# RR_MXR_v1.net
KiCad netlist of a schematic drawn in Altium Designer
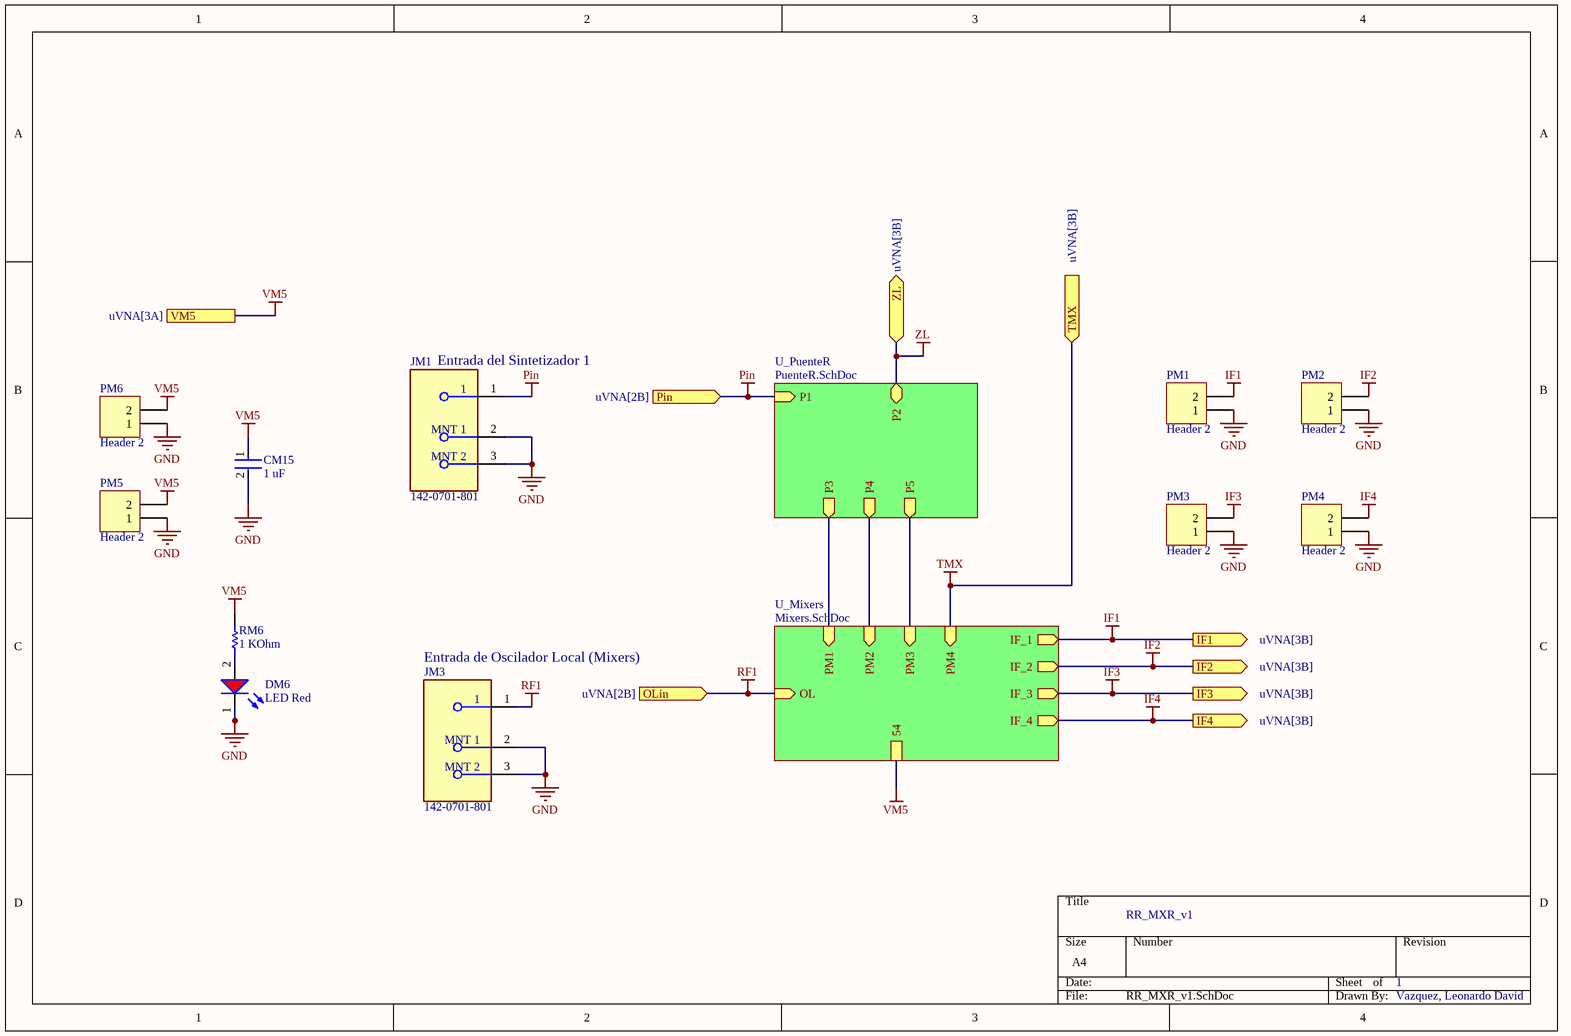
[diagram p0: RR_MXR_v1.SchDoc]

(export (version "E")
  (design (tool "Eeschema 10.0.6"))
  (components
    (comp (ref "CM15")
      (value "1 uF")
      (footprint "FP-CC0805-0_85-MFG")
      (description "CAP CER 0.1UF 50V X7R 0805")
      (fields (field (name "TOLERANCE") "0.1") (field (name "MANUFACTURER PART NUMBER") "CC0805KRX7R9BB104"))
      (libsource (lib "Altium Content Vault") (part "11868f565c42a9108669ba33697ecf6"))
    )
    (comp (ref "DM6")
      (value "LED Red")
      (footprint "WL-SMCW_0805_150080xx75000")
      (libsource (lib "Altium Content Vault") (part "LED_Red_2A-1K"))
    )
    (comp (ref "JM1")
      (value "142-0701-801")
      (footprint "FP-142-0701-801-MFG")
      (description "CONN SMA JACK STR 50OHM EDGE MNT")
      (libsource (lib "Altium Content Vault") (part "89929399afe843c8b6880c6cbd0f99a"))
    )
    (comp (ref "JM3")
      (value "142-0701-801")
      (footprint "FP-142-0701-801-MFG")
      (description "CONN SMA JACK STR 50OHM EDGE MNT")
      (libsource (lib "Altium Content Vault") (part "89929399afe843c8b6880c6cbd0f99a"))
    )
    (comp (ref "PM1")
      (value "Header 2")
      (footprint "HDR1X2")
      (description "Header, 2-Pin")
      (fields (field (name "PUBLISHER") "Altium Limited"))
      (libsource (lib "Miscellaneous Connectors") (part "Header 2"))
    )
    (comp (ref "PM2")
      (value "Header 2")
      (footprint "HDR1X2")
      (description "Header, 2-Pin")
      (fields (field (name "PUBLISHER") "Altium Limited"))
      (libsource (lib "Miscellaneous Connectors") (part "Header 2"))
    )
    (comp (ref "PM3")
      (value "Header 2")
      (footprint "HDR1X2")
      (description "Header, 2-Pin")
      (fields (field (name "PUBLISHER") "Altium Limited"))
      (libsource (lib "Miscellaneous Connectors") (part "Header 2"))
    )
    (comp (ref "PM4")
      (value "Header 2")
      (footprint "HDR1X2")
      (description "Header, 2-Pin")
      (fields (field (name "PUBLISHER") "Altium Limited"))
      (libsource (lib "Miscellaneous Connectors") (part "Header 2"))
    )
    (comp (ref "PM5")
      (value "Header 2")
      (footprint "HDR1X2")
      (description "Header, 2-Pin")
      (fields (field (name "PUBLISHER") "Altium Limited"))
      (libsource (lib "Miscellaneous Connectors") (part "Header 2"))
    )
    (comp (ref "PM6")
      (value "Header 2")
      (footprint "HDR1X2")
      (description "Header, 2-Pin")
      (fields (field (name "PUBLISHER") "Altium Limited"))
      (libsource (lib "Miscellaneous Connectors") (part "Header 2"))
    )
    (comp (ref "RM6")
      (value "1 KOhm")
      (footprint "RESC2013X60X40ML20T25")
      (fields (field (name "MANUFACTURER") "Panasonic") (field (name "PART NUMBER") "ERA6AEB101V"))
      (libsource (lib "Altium Content Vault") (part "RES"))
    )
  )
  (nets
    (net (code "4") (name "GND") (class "Default")
      (node (ref "CM15") (pin "2") (pinfunction "2_2") (pintype "passive"))
      (node (ref "DM6") (pin "1") (pinfunction "K_1") (pintype "passive"))
      (node (ref "JM1") (pin "2") (pinfunction "MNT_1_2") (pintype "passive"))
      (node (ref "JM1") (pin "3") (pinfunction "MNT_2_3") (pintype "passive"))
      (node (ref "JM3") (pin "2") (pinfunction "MNT_1_2") (pintype "passive"))
      (node (ref "JM3") (pin "3") (pinfunction "MNT_2_3") (pintype "passive"))
      (node (ref "PM1") (pin "1") (pinfunction "1_1") (pintype "passive"))
      (node (ref "PM2") (pin "1") (pinfunction "1_1") (pintype "passive"))
      (node (ref "PM3") (pin "1") (pinfunction "1_1") (pintype "passive"))
      (node (ref "PM4") (pin "1") (pinfunction "1_1") (pintype "passive"))
      (node (ref "PM5") (pin "1") (pinfunction "1_1") (pintype "passive"))
      (node (ref "PM6") (pin "1") (pinfunction "1_1") (pintype "passive"))
    )
    (net (code "5") (name "IF1") (class "Default")
      (node (ref "PM1") (pin "2") (pinfunction "2_2") (pintype "passive"))
    )
    (net (code "6") (name "IF2") (class "Default")
      (node (ref "PM2") (pin "2") (pinfunction "2_2") (pintype "passive"))
    )
    (net (code "7") (name "IF3") (class "Default")
      (node (ref "PM3") (pin "2") (pinfunction "2_2") (pintype "passive"))
    )
    (net (code "8") (name "IF4") (class "Default")
      (node (ref "PM4") (pin "2") (pinfunction "2_2") (pintype "passive"))
    )
    (net (code "9") (name "Net-(DM6-A)") (class "Default")
      (node (ref "DM6") (pin "2") (pinfunction "A_2") (pintype "passive"))
      (node (ref "RM6") (pin "1") (pinfunction "1_1") (pintype "passive"))
    )
    (net (code "10") (name "Pin") (class "Default")
      (node (ref "JM1") (pin "1") (pinfunction "1_1") (pintype "passive"))
    )
    (net (code "11") (name "RF1") (class "Default")
      (node (ref "JM3") (pin "1") (pinfunction "1_1") (pintype "passive"))
    )
    (net (code "13") (name "VM5") (class "Default")
      (node (ref "CM15") (pin "1") (pinfunction "1_1") (pintype "passive"))
      (node (ref "PM5") (pin "2") (pinfunction "2_2") (pintype "passive"))
      (node (ref "PM6") (pin "2") (pinfunction "2_2") (pintype "passive"))
      (node (ref "RM6") (pin "2") (pinfunction "2_2") (pintype "passive"))
    )
  )
)
